# Power.net
KiCad netlist of a schematic drawn in Altium Designer
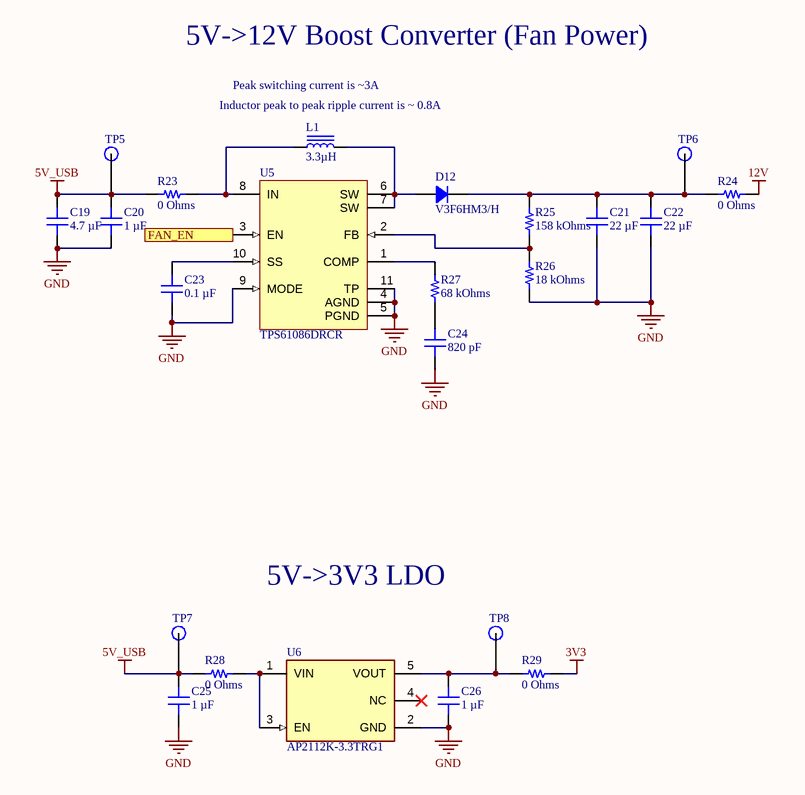
[diagram p0: Power.SchDoc]

(export (version "E")
  (design (tool "Eeschema 10.0.6"))
  (components
    (comp (ref "C19")
      (value "4.7 µF")
      (footprint "CAP 0603_1608")
      (description "CAP CER 4.7UF 10V X5R 0603")
      (fields
        (field (name "PART NUMBER") "CL10A475KP8NNNC")
        (field (name "MANUFACTURER") "Samsung Electro-Mechanics")
      )
      (libsource (lib "Celestial Altium Library - altium_library") (part "Capacitor"))
    )
    (comp (ref "C20")
      (value "1 µF")
      (footprint "CAP 0805_2012")
      (description "CAP CER 1UF 50V X7R 0805")
      (fields
        (field (name "PART NUMBER") "GCJ21BR71H105KA01L")
        (field (name "MANUFACTURER") "Murata Electronics")
      )
      (libsource (lib "Celestial Altium Library - altium_library") (part "Capacitor"))
    )
    (comp (ref "C21")
      (value "22 µF")
      (footprint "CAP 1206_3216 - 0.8MM")
      (description "CAP CER 22UF 16V X5R 1206")
      (fields
        (field (name "PART NUMBER") "CL31A226MOCLNNC")
        (field (name "MANUFACTURER") "Samsung Electro-Mechanics")
      )
      (libsource (lib "Celestial Altium Library - altium_library") (part "Capacitor"))
    )
    (comp (ref "C22")
      (value "22 µF")
      (footprint "CAP 1206_3216 - 0.8MM")
      (description "CAP CER 22UF 16V X5R 1206")
      (fields
        (field (name "PART NUMBER") "CL31A226MOCLNNC")
        (field (name "MANUFACTURER") "Samsung Electro-Mechanics")
      )
      (libsource (lib "Celestial Altium Library - altium_library") (part "Capacitor"))
    )
    (comp (ref "C23")
      (value "0.1 µF")
      (footprint "CAP 0603_1608")
      (description "CAP CER 0.1UF 50V X7R 0603")
      (fields (field (name "PART NUMBER") "C0603C104K5RAC7411") (field (name "MANUFACTURER") "KEMET"))
      (libsource (lib "Celestial Altium Library - altium_library") (part "Capacitor"))
    )
    (comp (ref "C24")
      (value "820 pF")
      (footprint "CAP 0603_1608")
      (description "CAP CER 820PF 50V X7R 0603")
      (fields (field (name "PART NUMBER") "C0603C821K5RACAUTO") (field (name "MANUFACTURER") "KEMET"))
      (libsource (lib "Celestial Altium Library - altium_library") (part "Capacitor"))
    )
    (comp (ref "C25")
      (value "1 µF")
      (footprint "CAP 0603_1608")
      (description "CAP CER 1UF 10V X7R 0603")
      (fields (field (name "PART NUMBER") "CC0603KRX7R6BB105") (field (name "MANUFACTURER") "Yageo"))
      (libsource (lib "Celestial Altium Library - altium_library") (part "Capacitor"))
    )
    (comp (ref "C26")
      (value "1 µF")
      (footprint "CAP 0603_1608")
      (description "CAP CER 1UF 10V X7R 0603")
      (fields (field (name "PART NUMBER") "CC0603KRX7R6BB105") (field (name "MANUFACTURER") "Yageo"))
      (libsource (lib "Celestial Altium Library - altium_library") (part "Capacitor"))
    )
    (comp (ref "D12")
      (value "V3F6HM3/H")
      (footprint "SMF DO-219AB")
      (description "3A,60V,SMF,TRENCH SKY RECT.")
      (fields (field (name "MANUFACTURER") "Vishay Semiconductor Diodes Division"))
      (libsource (lib "Celestial Altium Library - altium_library") (part "Diode"))
    )
    (comp (ref "L1")
      (value "3.3µH")
      (footprint "IND 1008_2520")
      (description "FIXED IND 3.3UH 1.6A 170 MOHM")
      (fields
        (field (name "PART NUMBER") "DFE252010F-3R3M=P2")
        (field (name "MANUFACTURER") "Murata Electronics")
      )
      (libsource (lib "Celestial Altium Library - altium_library") (part "Inductor"))
    )
    (comp (ref "R23")
      (value "0 Ohms")
      (footprint "RES 0603_1608")
      (description "RES 0 OHM JUMPER 0603")
      (fields
        (field (name "PART NUMBER") "TLRZ1JTTD")
        (field (name "MANUFACTURER") "KOA Speer Electronics, Inc.")
      )
      (libsource (lib "Celestial Altium Library - altium_library") (part "Resistor"))
    )
    (comp (ref "R24")
      (value "0 Ohms")
      (footprint "RES 0603_1608")
      (description "RES 0 OHM JUMPER 0603")
      (fields
        (field (name "PART NUMBER") "TLRZ1JTTD")
        (field (name "MANUFACTURER") "KOA Speer Electronics, Inc.")
      )
      (libsource (lib "Celestial Altium Library - altium_library") (part "Resistor"))
    )
    (comp (ref "R25")
      (value "158 kOhms")
      (footprint "RES 0603_1608")
      (description "RES 158K OHM 1% 1/10W 0603")
      (fields (field (name "PART NUMBER") "RC0603FR-07158KL") (field (name "MANUFACTURER") "Yageo"))
      (libsource (lib "Celestial Altium Library - altium_library") (part "Resistor"))
    )
    (comp (ref "R26")
      (value "18 kOhms")
      (footprint "RES 0603_1608")
      (description "RES 18K OHM 1% 1/10W 0603")
      (fields
        (field (name "PART NUMBER") "RMCF0603FT18K0")
        (field (name "MANUFACTURER") "Stackpole Electronics Inc")
      )
      (libsource (lib "Celestial Altium Library - altium_library") (part "Resistor"))
    )
    (comp (ref "R27")
      (value "68 kOhms")
      (footprint "RES 0603_1608")
      (description "RES 68K OHM 1% 1/4W 0603")
      (fields
        (field (name "PART NUMBER") "CRGP0603F68K")
        (field (name "MANUFACTURER") "TE Connectivity Passive Product")
      )
      (libsource (lib "Celestial Altium Library - altium_library") (part "Resistor"))
    )
    (comp (ref "R28")
      (value "0 Ohms")
      (footprint "RES 0603_1608")
      (description "RES 0 OHM JUMPER 0603")
      (fields
        (field (name "PART NUMBER") "TLRZ1JTTD")
        (field (name "MANUFACTURER") "KOA Speer Electronics, Inc.")
      )
      (libsource (lib "Celestial Altium Library - altium_library") (part "Resistor"))
    )
    (comp (ref "R29")
      (value "0 Ohms")
      (footprint "RES 0603_1608")
      (description "RES 0 OHM JUMPER 0603")
      (fields
        (field (name "PART NUMBER") "TLRZ1JTTD")
        (field (name "MANUFACTURER") "KOA Speer Electronics, Inc.")
      )
      (libsource (lib "Celestial Altium Library - altium_library") (part "Resistor"))
    )
    (comp (ref "TP5")
      (value "1.5mm Test Point")
      (footprint "1mm Test Point-Footprint-1")
      (description "1.5mm Test Point 0.75mm hole size")
      (libsource (lib "Americas- Environmental Engineering Club- University of Victoria") (part "1mm Test Point-Symbol-1"))
    )
    (comp (ref "TP6")
      (value "1.5mm Test Point")
      (footprint "1mm Test Point-Footprint-1")
      (description "1.5mm Test Point 0.75mm hole size")
      (libsource (lib "Americas- Environmental Engineering Club- University of Victoria") (part "1mm Test Point-Symbol-1"))
    )
    (comp (ref "TP7")
      (value "1.5mm Test Point")
      (footprint "1mm Test Point-Footprint-1")
      (description "1.5mm Test Point 0.75mm hole size")
      (libsource (lib "Americas- Environmental Engineering Club- University of Victoria") (part "1mm Test Point-Symbol-1"))
    )
    (comp (ref "TP8")
      (value "1.5mm Test Point")
      (footprint "1mm Test Point-Footprint-1")
      (description "1.5mm Test Point 0.75mm hole size")
      (libsource (lib "Americas- Environmental Engineering Club- University of Victoria") (part "1mm Test Point-Symbol-1"))
    )
    (comp (ref "U5")
      (value "TPS61086DRCR")
      (footprint "DRC0010A_V")
      (fields (field (name "MANUFACTURER") "Texas Instruments"))
      (libsource (lib "Altium Content Vault") (part "TI-TPS61086DRC10-2400X1650TP"))
    )
    (comp (ref "U6")
      (value "AP2112K-3.3TRG1")
      (footprint "FP-SOT25-IPC_A")
      (description "IC REG LINEAR 3.3V 600MA SOT25")
      (libsource (lib "Altium Content Vault") (part "c8ab751aee5229183125ab046a11caa"))
    )
  )
  (nets
    (net (code "1") (name "/FAN_EN") (class "Default")
      (node (ref "U5") (pin "3") (pinfunction "EN_3") (pintype "input"))
    )
    (net (code "2") (name "3V3") (class "Default")
      (node (ref "R29") (pin "2") (pinfunction "2_2") (pintype "passive"))
    )
    (net (code "3") (name "5V_USB") (class "Default")
      (node (ref "C19") (pin "2") (pinfunction "2_2") (pintype "passive"))
      (node (ref "C20") (pin "2") (pinfunction "2_2") (pintype "passive"))
      (node (ref "C25") (pin "2") (pinfunction "2_2") (pintype "passive"))
      (node (ref "R23") (pin "1") (pinfunction "1_1") (pintype "passive"))
      (node (ref "R28") (pin "1") (pinfunction "1_1") (pintype "passive"))
      (node (ref "TP5") (pin "1") (pinfunction "1_1") (pintype "passive"))
      (node (ref "TP7") (pin "1") (pinfunction "1_1") (pintype "passive"))
    )
    (net (code "4") (name "12V") (class "Default")
      (node (ref "R24") (pin "2") (pinfunction "2_2") (pintype "passive"))
    )
    (net (code "5") (name "GND") (class "Default")
      (node (ref "C19") (pin "1") (pinfunction "1_1") (pintype "passive"))
      (node (ref "C20") (pin "1") (pinfunction "1_1") (pintype "passive"))
      (node (ref "C21") (pin "1") (pinfunction "1_1") (pintype "passive"))
      (node (ref "C22") (pin "1") (pinfunction "1_1") (pintype "passive"))
      (node (ref "C23") (pin "1") (pinfunction "1_1") (pintype "passive"))
      (node (ref "C24") (pin "1") (pinfunction "1_1") (pintype "passive"))
      (node (ref "C25") (pin "1") (pinfunction "1_1") (pintype "passive"))
      (node (ref "C26") (pin "1") (pinfunction "1_1") (pintype "passive"))
      (node (ref "R26") (pin "1") (pinfunction "1_1") (pintype "passive"))
      (node (ref "U5") (pin "11") (pinfunction "TP_11") (pintype "power_in"))
      (node (ref "U5") (pin "4") (pinfunction "AGND_4") (pintype "power_in"))
      (node (ref "U5") (pin "5") (pinfunction "PGND_5") (pintype "power_in"))
      (node (ref "U5") (pin "9") (pinfunction "MODE_9") (pintype "input"))
      (node (ref "U6") (pin "2") (pinfunction "GND_2") (pintype "power_in"))
    )
    (net (code "6") (name "Net-(C21-Pad2)") (class "Default")
      (node (ref "C21") (pin "2") (pinfunction "2_2") (pintype "passive"))
      (node (ref "C22") (pin "2") (pinfunction "2_2") (pintype "passive"))
      (node (ref "D12") (pin "2") (pinfunction "2_2") (pintype "passive"))
      (node (ref "R24") (pin "1") (pinfunction "1_1") (pintype "passive"))
      (node (ref "R25") (pin "2") (pinfunction "2_2") (pintype "passive"))
      (node (ref "TP6") (pin "1") (pinfunction "1_1") (pintype "passive"))
    )
    (net (code "7") (name "Net-(C24-Pad2)") (class "Default")
      (node (ref "C24") (pin "2") (pinfunction "2_2") (pintype "passive"))
      (node (ref "R27") (pin "1") (pinfunction "1_1") (pintype "passive"))
    )
    (net (code "8") (name "Net-(D12-Pad1)") (class "Default")
      (node (ref "D12") (pin "1") (pinfunction "1_1") (pintype "passive"))
      (node (ref "L1") (pin "2") (pinfunction "2_2") (pintype "passive"))
      (node (ref "U5") (pin "6") (pinfunction "SW_6") (pintype "power_in"))
      (node (ref "U5") (pin "7") (pinfunction "SW_7") (pintype "power_in"))
    )
    (net (code "9") (name "Net-(U5-COMP)") (class "Default")
      (node (ref "R27") (pin "2") (pinfunction "2_2") (pintype "passive"))
      (node (ref "U5") (pin "1") (pinfunction "COMP_1") (pintype "passive"))
    )
    (net (code "10") (name "Net-(U5-FB)") (class "Default")
      (node (ref "R25") (pin "1") (pinfunction "1_1") (pintype "passive"))
      (node (ref "R26") (pin "2") (pinfunction "2_2") (pintype "passive"))
      (node (ref "U5") (pin "2") (pinfunction "FB_2") (pintype "input"))
    )
    (net (code "11") (name "Net-(U5-IN)") (class "Default")
      (node (ref "L1") (pin "1") (pinfunction "1_1") (pintype "passive"))
      (node (ref "R23") (pin "2") (pinfunction "2_2") (pintype "passive"))
      (node (ref "U5") (pin "8") (pinfunction "IN_8") (pintype "power_in"))
    )
    (net (code "12") (name "Net-(U5-SS)") (class "Default")
      (node (ref "C23") (pin "2") (pinfunction "2_2") (pintype "passive"))
      (node (ref "U5") (pin "10") (pinfunction "SS_10") (pintype "input"))
    )
    (net (code "13") (name "Net-(U6-EN)") (class "Default")
      (node (ref "R28") (pin "2") (pinfunction "2_2") (pintype "passive"))
      (node (ref "U6") (pin "1") (pinfunction "VIN_1") (pintype "power_in"))
      (node (ref "U6") (pin "3") (pinfunction "EN_3") (pintype "input"))
    )
    (net (code "14") (name "Net-(U6-VOUT)") (class "Default")
      (node (ref "C26") (pin "2") (pinfunction "2_2") (pintype "passive"))
      (node (ref "R29") (pin "1") (pinfunction "1_1") (pintype "passive"))
      (node (ref "TP8") (pin "1") (pinfunction "1_1") (pintype "passive"))
      (node (ref "U6") (pin "5") (pinfunction "VOUT_5") (pintype "power_in"))
    )
    (net (code "15") (name "unconnected-(U6-NC-Pad4)") (class "Default")
      (node (ref "U6") (pin "4") (pinfunction "NC_4") (pintype "passive+no_connect"))
    )
  )
)
